# H-brigde_connector.net
KiCad netlist of a schematic drawn in Altium Designer
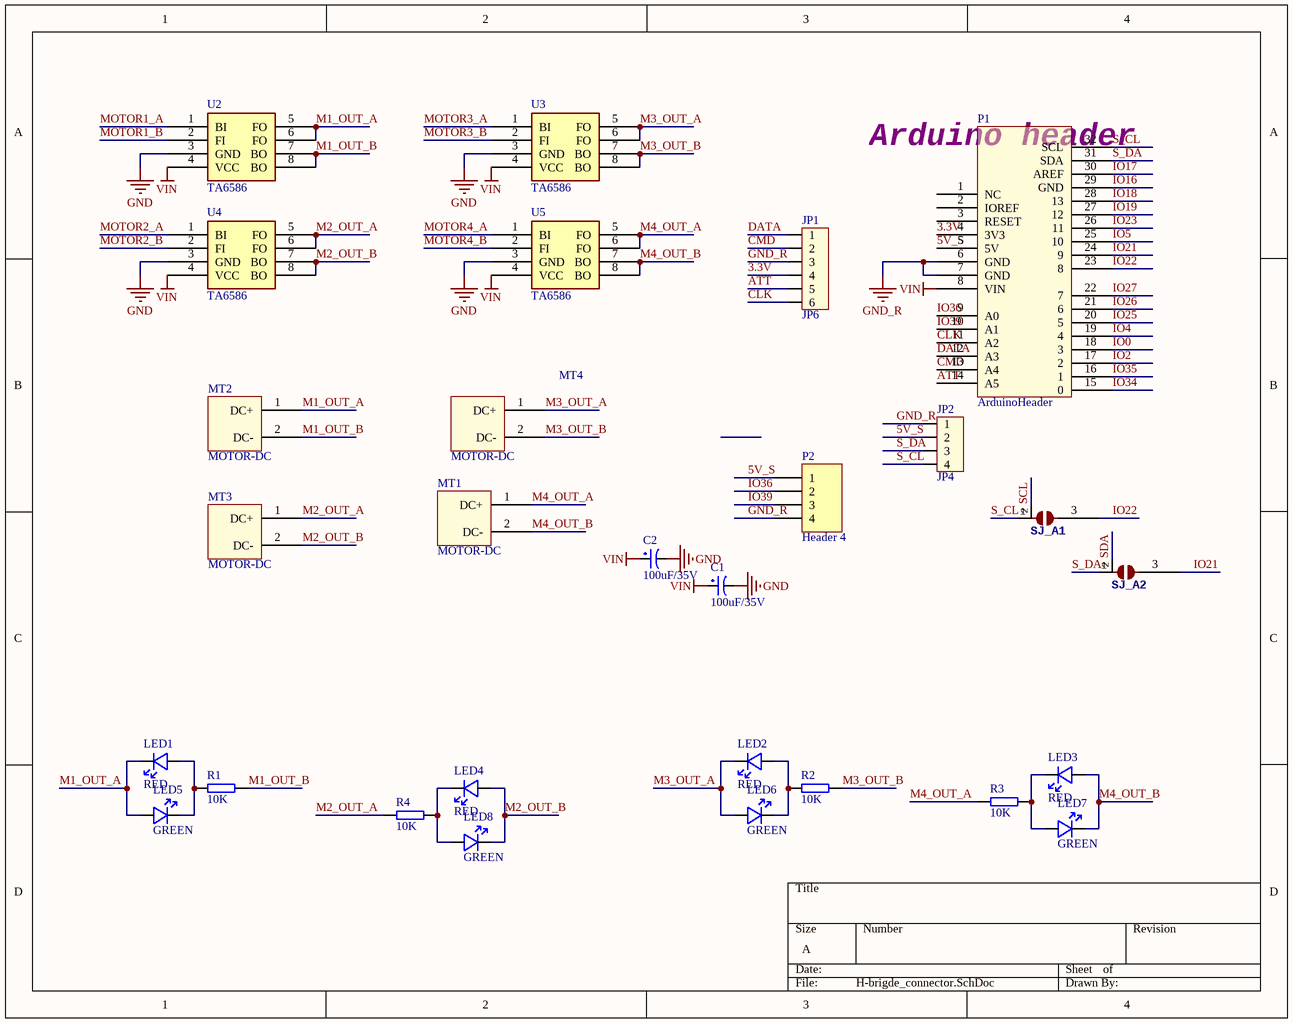
[diagram p0: H-brigde_connector.SchDoc]

(export (version "E")
  (design (tool "Eeschema 10.0.6"))
  (components
    (comp (ref "C1")
      (value "100uF/35V")
      (footprint "CP1.5/3.4")
      (description "Cap 100uF/35V - 470uF/16V")
      (libsource (lib "My Library") (part "CP3"))
    )
    (comp (ref "C2")
      (value "100uF/35V")
      (footprint "CP1.5/3.4")
      (description "Cap 100uF/35V - 470uF/16V")
      (libsource (lib "My Library") (part "CP3"))
    )
    (comp (ref "JP1")
      (value "JP6")
      (footprint "CON6")
      (description "Connector 6")
      (libsource (lib "My Library") (part "Con6"))
    )
    (comp (ref "JP2")
      (value "JP4")
      (footprint "CONN-TH_XH2.54-4AW")
      (description "Connector 4")
      (libsource (lib "My Library") (part "Con4"))
    )
    (comp (ref "LED1")
      (value "RED")
      (footprint "SMT0603P")
      (description "LED SM 0603 RED 1V95 FWD VOLTAGE")
      (libsource (lib "electronpowered") (part "LNJ237W82RA"))
    )
    (comp (ref "LED2")
      (value "RED")
      (footprint "SMT0603P")
      (description "LED SM 0603 RED 1V95 FWD VOLTAGE")
      (libsource (lib "electronpowered") (part "LNJ237W82RA"))
    )
    (comp (ref "LED3")
      (value "RED")
      (footprint "SMT0603P")
      (description "LED SM 0603 RED 1V95 FWD VOLTAGE")
      (libsource (lib "electronpowered") (part "LNJ237W82RA"))
    )
    (comp (ref "LED4")
      (value "RED")
      (footprint "SMT0603P")
      (description "LED SM 0603 RED 1V95 FWD VOLTAGE")
      (libsource (lib "electronpowered") (part "LNJ237W82RA"))
    )
    (comp (ref "LED5")
      (value "GREEN")
      (footprint "SMT0603P")
      (description "LED SM 0603 GREEN 1V95 FWD VOLTAGE")
      (libsource (lib "electronpowered") (part "LNJ337W83RA"))
    )
    (comp (ref "LED6")
      (value "GREEN")
      (footprint "SMT0603P")
      (description "LED SM 0603 GREEN 1V95 FWD VOLTAGE")
      (libsource (lib "electronpowered") (part "LNJ337W83RA"))
    )
    (comp (ref "LED7")
      (value "GREEN")
      (footprint "SMT0603P")
      (description "LED SM 0603 GREEN 1V95 FWD VOLTAGE")
      (libsource (lib "electronpowered") (part "LNJ337W83RA"))
    )
    (comp (ref "LED8")
      (value "GREEN")
      (footprint "SMT0603P")
      (description "LED SM 0603 GREEN 1V95 FWD VOLTAGE")
      (libsource (lib "electronpowered") (part "LNJ337W83RA"))
    )
    (comp (ref "MT1")
      (value "MOTOR-DC")
      (footprint "CON2-5.08DC")
      (libsource (lib "RASHBERRY_EXTERN") (part "MOTOR-DC"))
    )
    (comp (ref "MT2")
      (value "MOTOR-DC")
      (footprint "CON2-5.08DC")
      (libsource (lib "RASHBERRY_EXTERN") (part "MOTOR-DC"))
    )
    (comp (ref "MT3")
      (value "MOTOR-DC")
      (footprint "CON2-5.08DC")
      (libsource (lib "RASHBERRY_EXTERN") (part "MOTOR-DC"))
    )
    (comp (ref "MT4")
      (value "MOTOR-DC")
      (footprint "CON2-5.08DC")
      (libsource (lib "RASHBERRY_EXTERN") (part "MOTOR-DC"))
    )
    (comp (ref "P1")
      (value "ArduinoHeader")
      (footprint "ArduinoClone2")
      (libsource (lib "electronpowered") (part "ArduinoHeader"))
    )
    (comp (ref "P2")
      (value "Header 4")
      (footprint "HDR1X4")
      (description "Header, 4-Pin")
      (fields (field (name "PUBLISHER") "Altium Limited"))
      (libsource (lib "Miscellaneous Connectors") (part "Header 4"))
    )
    (comp (ref "R1")
      (value "10K")
      (footprint "SMT0603")
      (description "RES SM 0603 10K")
      (fields (field (name "Comment") "Resistor"))
      (libsource (lib "electronpowered") (part "RES-SM-0603-10K"))
    )
    (comp (ref "R2")
      (value "10K")
      (footprint "SMT0603")
      (description "RES SM 0603 10K")
      (fields (field (name "Comment") "Resistor"))
      (libsource (lib "electronpowered") (part "RES-SM-0603-10K"))
    )
    (comp (ref "R3")
      (value "10K")
      (footprint "SMT0603")
      (description "RES SM 0603 10K")
      (fields (field (name "Comment") "Resistor"))
      (libsource (lib "electronpowered") (part "RES-SM-0603-10K"))
    )
    (comp (ref "R4")
      (value "10K")
      (footprint "SMT0603")
      (description "RES SM 0603 10K")
      (fields (field (name "Comment") "Resistor"))
      (libsource (lib "electronpowered") (part "RES-SM-0603-10K"))
    )
    (comp (ref "SJ_A1")
      (value "SOLDERJUMPERREFLOW_NOPASTE")
      (footprint "SOLDERJUMPER_REFLOW_NOPASTE")
      (libsource (lib "Adafruit PCA9685 rev C") (part "SOLDERJUMPERREFLOW_NOPASTE"))
    )
    (comp (ref "SJ_A2")
      (value "SOLDERJUMPERREFLOW_NOPASTE")
      (footprint "SOLDERJUMPER_REFLOW_NOPASTE")
      (libsource (lib "Adafruit PCA9685 rev C") (part "SOLDERJUMPERREFLOW_NOPASTE"))
    )
    (comp (ref "U2")
      (value "TA6586")
      (footprint "DIP.100/8/W.300/L.400")
      (libsource (lib "TA6586") (part "TA6586"))
    )
    (comp (ref "U3")
      (value "TA6586")
      (footprint "DIP.100/8/W.300/L.400")
      (libsource (lib "TA6586") (part "TA6586"))
    )
    (comp (ref "U4")
      (value "TA6586")
      (footprint "DIP.100/8/W.300/L.400")
      (libsource (lib "TA6586") (part "TA6586"))
    )
    (comp (ref "U5")
      (value "TA6586")
      (footprint "DIP.100/8/W.300/L.400")
      (libsource (lib "TA6586") (part "TA6586"))
    )
  )
  (nets
    (net (code "1") (name "/3.3V") (class "Default")
      (node (ref "JP1") (pin "4") (pinfunction "4_4") (pintype "passive"))
      (node (ref "P1") (pin "4") (pinfunction "3V3_4") (pintype "passive"))
    )
    (net (code "2") (name "/5V_S") (class "Default")
      (node (ref "JP2") (pin "2") (pinfunction "2_2") (pintype "passive"))
      (node (ref "P1") (pin "5") (pinfunction "5V_5") (pintype "passive"))
      (node (ref "P2") (pin "1") (pinfunction "1_1") (pintype "passive"))
    )
    (net (code "3") (name "/ATT") (class "Default")
      (node (ref "JP1") (pin "5") (pinfunction "5_5") (pintype "passive"))
      (node (ref "P1") (pin "14") (pinfunction "A5_14") (pintype "passive"))
    )
    (net (code "4") (name "/CLK") (class "Default")
      (node (ref "JP1") (pin "6") (pinfunction "6_6") (pintype "passive"))
      (node (ref "P1") (pin "11") (pinfunction "A2_11") (pintype "passive"))
    )
    (net (code "5") (name "/CMD") (class "Default")
      (node (ref "JP1") (pin "2") (pinfunction "2_2") (pintype "passive"))
      (node (ref "P1") (pin "13") (pinfunction "A4_13") (pintype "passive"))
    )
    (net (code "6") (name "/DATA") (class "Default")
      (node (ref "JP1") (pin "1") (pinfunction "1_1") (pintype "passive"))
      (node (ref "P1") (pin "12") (pinfunction "A3_12") (pintype "passive"))
    )
    (net (code "7") (name "/IO0") (class "Default")
      (node (ref "P1") (pin "18") (pinfunction "3_18") (pintype "passive"))
    )
    (net (code "8") (name "/IO2") (class "Default")
      (node (ref "P1") (pin "17") (pinfunction "2_17") (pintype "passive"))
    )
    (net (code "9") (name "/IO4") (class "Default")
      (node (ref "P1") (pin "19") (pinfunction "4_19") (pintype "passive"))
    )
    (net (code "10") (name "/IO5") (class "Default")
      (node (ref "P1") (pin "25") (pinfunction "10_25") (pintype "passive"))
    )
    (net (code "11") (name "/IO16") (class "Default")
      (node (ref "P1") (pin "29") (pinfunction "GND_29") (pintype "passive"))
    )
    (net (code "12") (name "/IO17") (class "Default")
      (node (ref "P1") (pin "30") (pinfunction "AREF_30") (pintype "passive"))
    )
    (net (code "13") (name "/IO18") (class "Default")
      (node (ref "P1") (pin "28") (pinfunction "13_28") (pintype "passive"))
    )
    (net (code "14") (name "/IO19") (class "Default")
      (node (ref "P1") (pin "27") (pinfunction "12_27") (pintype "passive"))
    )
    (net (code "15") (name "/IO21") (class "Default")
      (node (ref "P1") (pin "24") (pinfunction "9_24") (pintype "passive"))
      (node (ref "SJ_A2") (pin "3") (pinfunction "3_3") (pintype "passive"))
    )
    (net (code "16") (name "/IO22") (class "Default")
      (node (ref "P1") (pin "23") (pinfunction "8_23") (pintype "passive"))
      (node (ref "SJ_A1") (pin "3") (pinfunction "3_3") (pintype "passive"))
    )
    (net (code "17") (name "/IO23") (class "Default")
      (node (ref "P1") (pin "26") (pinfunction "11_26") (pintype "passive"))
    )
    (net (code "18") (name "/IO25") (class "Default")
      (node (ref "P1") (pin "20") (pinfunction "5_20") (pintype "passive"))
    )
    (net (code "19") (name "/IO26") (class "Default")
      (node (ref "P1") (pin "21") (pinfunction "6_21") (pintype "passive"))
    )
    (net (code "20") (name "/IO27") (class "Default")
      (node (ref "P1") (pin "22") (pinfunction "7_22") (pintype "passive"))
    )
    (net (code "21") (name "/IO34") (class "Default")
      (node (ref "P1") (pin "15") (pinfunction "0_15") (pintype "passive"))
    )
    (net (code "22") (name "/IO35") (class "Default")
      (node (ref "P1") (pin "16") (pinfunction "1_16") (pintype "passive"))
    )
    (net (code "23") (name "/IO36") (class "Default")
      (node (ref "P1") (pin "9") (pinfunction "A0_9") (pintype "passive"))
      (node (ref "P2") (pin "2") (pinfunction "2_2") (pintype "passive"))
    )
    (net (code "24") (name "/IO39") (class "Default")
      (node (ref "P1") (pin "10") (pinfunction "A1_10") (pintype "passive"))
      (node (ref "P2") (pin "3") (pinfunction "3_3") (pintype "passive"))
    )
    (net (code "25") (name "/M1_OUT_A") (class "Default")
      (node (ref "LED1") (pin "2") (pinfunction "2_2") (pintype "passive"))
      (node (ref "LED5") (pin "1") (pinfunction "1_1") (pintype "passive"))
      (node (ref "MT2") (pin "1") (pinfunction "DC+_1") (pintype "passive"))
      (node (ref "U2") (pin "5") (pinfunction "FO_5") (pintype "passive"))
      (node (ref "U2") (pin "6") (pinfunction "FO_6") (pintype "passive"))
    )
    (net (code "26") (name "/M1_OUT_B") (class "Default")
      (node (ref "MT2") (pin "2") (pinfunction "DC-_2") (pintype "passive"))
      (node (ref "R1") (pin "2") (pinfunction "2_2") (pintype "passive"))
      (node (ref "U2") (pin "7") (pinfunction "BO_7") (pintype "passive"))
      (node (ref "U2") (pin "8") (pinfunction "BO_8") (pintype "passive"))
    )
    (net (code "27") (name "/M2_OUT_A") (class "Default")
      (node (ref "MT3") (pin "1") (pinfunction "DC+_1") (pintype "passive"))
      (node (ref "R4") (pin "1") (pinfunction "1_1") (pintype "passive"))
      (node (ref "U4") (pin "5") (pinfunction "FO_5") (pintype "passive"))
      (node (ref "U4") (pin "6") (pinfunction "FO_6") (pintype "passive"))
    )
    (net (code "28") (name "/M2_OUT_B") (class "Default")
      (node (ref "LED4") (pin "1") (pinfunction "1_1") (pintype "passive"))
      (node (ref "LED8") (pin "2") (pinfunction "2_2") (pintype "passive"))
      (node (ref "MT3") (pin "2") (pinfunction "DC-_2") (pintype "passive"))
      (node (ref "U4") (pin "7") (pinfunction "BO_7") (pintype "passive"))
      (node (ref "U4") (pin "8") (pinfunction "BO_8") (pintype "passive"))
    )
    (net (code "29") (name "/M3_OUT_A") (class "Default")
      (node (ref "LED2") (pin "2") (pinfunction "2_2") (pintype "passive"))
      (node (ref "LED6") (pin "1") (pinfunction "1_1") (pintype "passive"))
      (node (ref "MT4") (pin "1") (pinfunction "DC+_1") (pintype "passive"))
      (node (ref "U3") (pin "5") (pinfunction "FO_5") (pintype "passive"))
      (node (ref "U3") (pin "6") (pinfunction "FO_6") (pintype "passive"))
    )
    (net (code "30") (name "/M3_OUT_B") (class "Default")
      (node (ref "MT4") (pin "2") (pinfunction "DC-_2") (pintype "passive"))
      (node (ref "R2") (pin "2") (pinfunction "2_2") (pintype "passive"))
      (node (ref "U3") (pin "7") (pinfunction "BO_7") (pintype "passive"))
      (node (ref "U3") (pin "8") (pinfunction "BO_8") (pintype "passive"))
    )
    (net (code "31") (name "/M4_OUT_A") (class "Default")
      (node (ref "MT1") (pin "1") (pinfunction "DC+_1") (pintype "passive"))
      (node (ref "R3") (pin "1") (pinfunction "1_1") (pintype "passive"))
      (node (ref "U5") (pin "5") (pinfunction "FO_5") (pintype "passive"))
      (node (ref "U5") (pin "6") (pinfunction "FO_6") (pintype "passive"))
    )
    (net (code "32") (name "/M4_OUT_B") (class "Default")
      (node (ref "LED3") (pin "1") (pinfunction "1_1") (pintype "passive"))
      (node (ref "LED7") (pin "2") (pinfunction "2_2") (pintype "passive"))
      (node (ref "MT1") (pin "2") (pinfunction "DC-_2") (pintype "passive"))
      (node (ref "U5") (pin "7") (pinfunction "BO_7") (pintype "passive"))
      (node (ref "U5") (pin "8") (pinfunction "BO_8") (pintype "passive"))
    )
    (net (code "33") (name "/MOTOR1_A") (class "Default")
      (node (ref "U2") (pin "1") (pinfunction "BI_1") (pintype "passive"))
    )
    (net (code "34") (name "/MOTOR1_B") (class "Default")
      (node (ref "U2") (pin "2") (pinfunction "FI_2") (pintype "passive"))
    )
    (net (code "35") (name "/MOTOR2_A") (class "Default")
      (node (ref "U4") (pin "1") (pinfunction "BI_1") (pintype "passive"))
    )
    (net (code "36") (name "/MOTOR2_B") (class "Default")
      (node (ref "U4") (pin "2") (pinfunction "FI_2") (pintype "passive"))
    )
    (net (code "37") (name "/MOTOR3_A") (class "Default")
      (node (ref "U3") (pin "1") (pinfunction "BI_1") (pintype "passive"))
    )
    (net (code "38") (name "/MOTOR3_B") (class "Default")
      (node (ref "U3") (pin "2") (pinfunction "FI_2") (pintype "passive"))
    )
    (net (code "39") (name "/MOTOR4_A") (class "Default")
      (node (ref "U5") (pin "1") (pinfunction "BI_1") (pintype "passive"))
    )
    (net (code "40") (name "/MOTOR4_B") (class "Default")
      (node (ref "U5") (pin "2") (pinfunction "FI_2") (pintype "passive"))
    )
    (net (code "41") (name "/SCL") (class "Default")
      (node (ref "SJ_A1") (pin "2") (pinfunction "2_2") (pintype "passive"))
    )
    (net (code "42") (name "/SDA") (class "Default")
      (node (ref "SJ_A2") (pin "2") (pinfunction "2_2") (pintype "passive"))
    )
    (net (code "43") (name "/S_CL") (class "Default")
      (node (ref "JP2") (pin "4") (pinfunction "4_4") (pintype "passive"))
      (node (ref "P1") (pin "32") (pinfunction "SCL_32") (pintype "passive"))
      (node (ref "SJ_A1") (pin "1") (pinfunction "1_1") (pintype "passive"))
    )
    (net (code "44") (name "/S_DA") (class "Default")
      (node (ref "JP2") (pin "3") (pinfunction "3_3") (pintype "passive"))
      (node (ref "P1") (pin "31") (pinfunction "SDA_31") (pintype "passive"))
      (node (ref "SJ_A2") (pin "1") (pinfunction "1_1") (pintype "passive"))
    )
    (net (code "45") (name "GND") (class "Default")
      (node (ref "C1") (pin "2") (pinfunction "2_2") (pintype "passive"))
      (node (ref "C2") (pin "2") (pinfunction "2_2") (pintype "passive"))
      (node (ref "U2") (pin "3") (pinfunction "GND_3") (pintype "passive"))
      (node (ref "U3") (pin "3") (pinfunction "GND_3") (pintype "passive"))
      (node (ref "U4") (pin "3") (pinfunction "GND_3") (pintype "passive"))
      (node (ref "U5") (pin "3") (pinfunction "GND_3") (pintype "passive"))
    )
    (net (code "46") (name "GND_R") (class "Default")
      (node (ref "JP1") (pin "3") (pinfunction "3_3") (pintype "passive"))
      (node (ref "JP2") (pin "1") (pinfunction "1_1") (pintype "passive"))
      (node (ref "P1") (pin "6") (pinfunction "GND_6") (pintype "passive"))
      (node (ref "P1") (pin "7") (pinfunction "GND_7") (pintype "passive"))
      (node (ref "P2") (pin "4") (pinfunction "4_4") (pintype "passive"))
    )
    (net (code "47") (name "Net-(LED1-Pad1)") (class "Default")
      (node (ref "LED1") (pin "1") (pinfunction "1_1") (pintype "passive"))
      (node (ref "LED5") (pin "2") (pinfunction "2_2") (pintype "passive"))
      (node (ref "R1") (pin "1") (pinfunction "1_1") (pintype "passive"))
    )
    (net (code "48") (name "Net-(LED2-Pad1)") (class "Default")
      (node (ref "LED2") (pin "1") (pinfunction "1_1") (pintype "passive"))
      (node (ref "LED6") (pin "2") (pinfunction "2_2") (pintype "passive"))
      (node (ref "R2") (pin "1") (pinfunction "1_1") (pintype "passive"))
    )
    (net (code "49") (name "Net-(LED3-Pad2)") (class "Default")
      (node (ref "LED3") (pin "2") (pinfunction "2_2") (pintype "passive"))
      (node (ref "LED7") (pin "1") (pinfunction "1_1") (pintype "passive"))
      (node (ref "R3") (pin "2") (pinfunction "2_2") (pintype "passive"))
    )
    (net (code "50") (name "Net-(LED4-Pad2)") (class "Default")
      (node (ref "LED4") (pin "2") (pinfunction "2_2") (pintype "passive"))
      (node (ref "LED8") (pin "1") (pinfunction "1_1") (pintype "passive"))
      (node (ref "R4") (pin "2") (pinfunction "2_2") (pintype "passive"))
    )
    (net (code "51") (name "VIN") (class "Default")
      (node (ref "C1") (pin "1") (pinfunction "1_1") (pintype "passive"))
      (node (ref "C2") (pin "1") (pinfunction "1_1") (pintype "passive"))
      (node (ref "P1") (pin "8") (pinfunction "VIN_8") (pintype "passive"))
      (node (ref "U2") (pin "4") (pinfunction "VCC_4") (pintype "passive"))
      (node (ref "U3") (pin "4") (pinfunction "VCC_4") (pintype "passive"))
      (node (ref "U4") (pin "4") (pinfunction "VCC_4") (pintype "passive"))
      (node (ref "U5") (pin "4") (pinfunction "VCC_4") (pintype "passive"))
    )
    (net (code "52") (name "unconnected-(P1-IOREF-Pad2)") (class "Default")
      (node (ref "P1") (pin "2") (pinfunction "IOREF_2") (pintype "passive"))
    )
    (net (code "53") (name "unconnected-(P1-NC-Pad1)") (class "Default")
      (node (ref "P1") (pin "1") (pinfunction "NC_1") (pintype "passive"))
    )
    (net (code "54") (name "unconnected-(P1-RESET-Pad3)") (class "Default")
      (node (ref "P1") (pin "3") (pinfunction "RESET_3") (pintype "passive"))
    )
  )
)
